# ultrasonic_sensor.net
KiCad netlist of a schematic drawn in Altium Designer
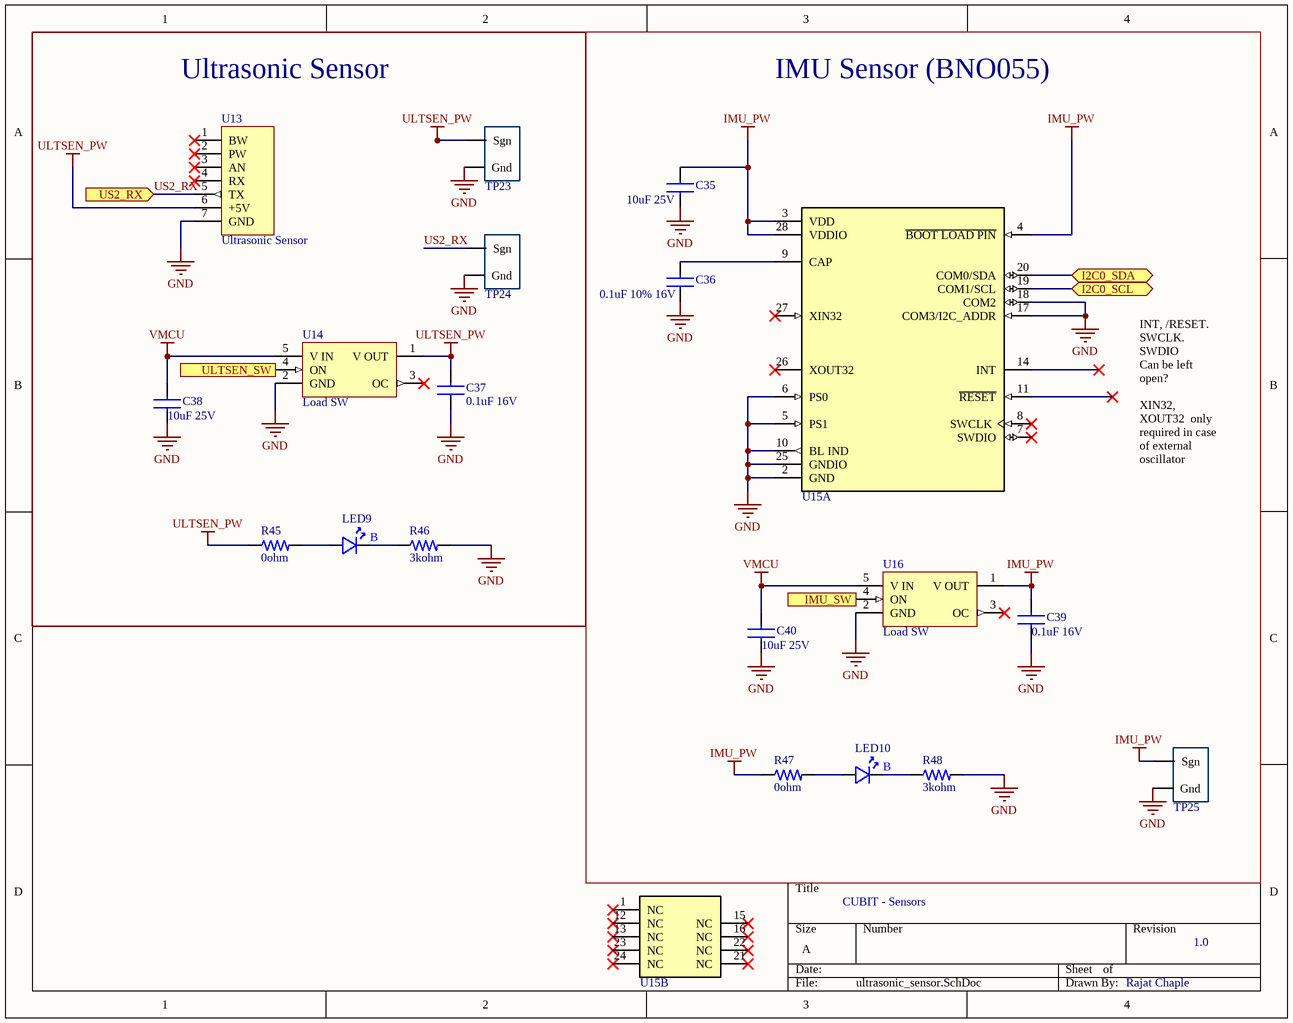
[diagram p0: ultrasonic_sensor.SchDoc]

(export (version "E")
  (design (tool "Eeschema 10.0.6"))
  (components
    (comp (ref "C35")
      (value "10uF 25V")
      (footprint "CAP_0805_02X125")
      (description "Cap 0805 25 V 10 uF ±20% Tolerance X5R Monolithic Ceramic Chip Capacitor")
      (fields
        (field (name "MANUFACTURER") "Murata")
        (field (name "MANUFACTURER PART NUMBER") "GRM21BR61E106KA73K")
      )
      (libsource (lib "LPEDT_proj_lib") (part "GRM21BR61E106KA73K"))
    )
    (comp (ref "C36")
      (value "0.1uF 10% 16V")
      (footprint "CAP_0805_02X125")
      (description "Cap Ceramic 0.1uF 16V X7R 10% SMD 0805 125°C Paper T/R")
      (fields
        (field (name "MANUFACTURER") "KEMET")
        (field (name "MANUFACTURER PART NUMBER") "C0805C104K4RACAUTO")
      )
      (libsource (lib "LPEDT_proj_lib") (part "C0805C104K4RACAUTO"))
    )
    (comp (ref "C37")
      (value "0.1uF 16V")
      (footprint "CAP_0805_02X125")
      (description "Cap Ceramic 0.1uF 16V X7R 10% SMD 0805 125°C Paper T/R")
      (fields
        (field (name "MANUFACTURER") "KEMET")
        (field (name "MANUFACTURER PART NUMBER") "C0805C104K4RACAUTO")
      )
      (libsource (lib "LPEDT_proj_lib") (part "C0805C104K4RACAUTO"))
    )
    (comp (ref "C38")
      (value "10uF 25V")
      (footprint "CAP_0805_02X125")
      (description "Cap 0805 25 V 10 uF ±20% Tolerance X5R Monolithic Ceramic Chip Capacitor")
      (fields
        (field (name "MANUFACTURER") "Murata")
        (field (name "MANUFACTURER PART NUMBER") "GRM21BR61E106KA73K")
      )
      (libsource (lib "LPEDT_proj_lib") (part "GRM21BR61E106KA73K"))
    )
    (comp (ref "C39")
      (value "0.1uF 16V")
      (footprint "CAP_0805_02X125")
      (description "Cap Ceramic 0.1uF 16V X7R 10% SMD 0805 125°C Paper T/R")
      (fields
        (field (name "MANUFACTURER") "KEMET")
        (field (name "MANUFACTURER PART NUMBER") "C0805C104K4RACAUTO")
      )
      (libsource (lib "LPEDT_proj_lib") (part "C0805C104K4RACAUTO"))
    )
    (comp (ref "C40")
      (value "10uF 25V")
      (footprint "CAP_0805_02X125")
      (description "Cap 0805 25 V 10 uF ±20% Tolerance X5R Monolithic Ceramic Chip Capacitor")
      (fields
        (field (name "MANUFACTURER") "Murata")
        (field (name "MANUFACTURER PART NUMBER") "GRM21BR61E106KA73K")
      )
      (libsource (lib "LPEDT_proj_lib") (part "GRM21BR61E106KA73K"))
    )
    (comp (ref "LED9")
      (value "150060BS75000")
      (footprint "LED_0603_RED_WL-SMCW")
      (description "Led, Blue, 470 Nm, 3.2 V, 30 Ma, 145 Mcd Rohs Compliant: Yes")
      (fields (field (name "MANUFACTURER") "Wurth Electronics"))
      (libsource (lib "LPEDT_proj_lib") (part "150060BS75000"))
    )
    (comp (ref "LED10")
      (value "150060BS75000")
      (footprint "LED_0603_RED_WL-SMCW")
      (description "Led, Blue, 470 Nm, 3.2 V, 30 Ma, 145 Mcd Rohs Compliant: Yes")
      (fields (field (name "MANUFACTURER") "Wurth Electronics"))
      (libsource (lib "LPEDT_proj_lib") (part "150060BS75000"))
    )
    (comp (ref "R45")
      (value "0ohm")
      (footprint "CAP_0402_1mm")
      (description "Res 0 Ohms ±5% 0.063 W 0402 Thick Film Surface Mount Chip Resistor")
      (fields
        (field (name "MANUFACTURER") "Samsung")
        (field (name "MANUFACTURER PART NUMBER") "RC1005J000CS")
      )
      (libsource (lib "LPEDT_proj_lib") (part "RC1005J000CS"))
    )
    (comp (ref "R46")
      (value "3kohm")
      (footprint "CAP_0603_1MM")
      (description "Res 3000Ω ± 1.00% 0.1W ± 100ppm/℃ 0603")
      (fields
        (field (name "MANUFACTURER") "Yageo")
        (field (name "MANUFACTURER PART NUMBER") "RC0603FR-073KL")
      )
      (libsource (lib "LPEDT_proj_lib") (part "RC0603FR-073KL"))
    )
    (comp (ref "R47")
      (value "0ohm")
      (footprint "CAP_0402_1mm")
      (description "Res 0 Ohms ±5% 0.063 W 0402 Thick Film Surface Mount Chip Resistor")
      (fields
        (field (name "MANUFACTURER") "Samsung")
        (field (name "MANUFACTURER PART NUMBER") "RC1005J000CS")
      )
      (libsource (lib "LPEDT_proj_lib") (part "RC1005J000CS"))
    )
    (comp (ref "R48")
      (value "3kohm")
      (footprint "CAP_0603_1MM")
      (description "Res 3000Ω ± 1.00% 0.1W ± 100ppm/℃ 0603")
      (fields
        (field (name "MANUFACTURER") "Yageo")
        (field (name "MANUFACTURER PART NUMBER") "RC0603FR-073KL")
      )
      (libsource (lib "LPEDT_proj_lib") (part "RC0603FR-073KL"))
    )
    (comp (ref "TP23")
      (value "10x Probe TP")
      (footprint "TP10x_Probe")
      (description "Test Point 300 mil centers")
      (libsource (lib "LPEDT_proj_lib") (part "TP_10x_Probe"))
    )
    (comp (ref "TP24")
      (value "10x Probe TP")
      (footprint "TP10x_Probe")
      (description "Test Point 300 mil centers")
      (libsource (lib "LPEDT_proj_lib") (part "TP_10x_Probe"))
    )
    (comp (ref "TP25")
      (value "10x Probe TP")
      (footprint "TP10x_Probe")
      (description "Test Point 300 mil centers")
      (libsource (lib "LPEDT_proj_lib") (part "TP_10x_Probe"))
    )
    (comp (ref "U13")
      (value "Ultrasonic Sensor")
      (footprint "7_PIN_100MIL")
      (libsource (lib "LPEDT_proj_lib") (part "Ultrasonic Sensor"))
    )
    (comp (ref "U14")
      (value "Load SW")
      (footprint "SOT65P210X110-5N")
      (description "5.5-V, 0.1-A, 500-mΩ, load switch with current limit and active low enable 5-SC70 -40 to 85")
      (fields
        (field (name "MANUFACTURER") "Texas Instruments")
        (field (name "MANUFACTURER PART NUMBER") "TPS22942DCKR")
      )
      (libsource (lib "LPEDT_proj_lib") (part "TPS22942DCKR"))
    )
    (comp (ref "U15")
      (value "BNO005")
      (footprint "LGA28R50P4X10_380X520X100")
      (libsource (lib "LPEDT_proj_lib") (part "BNO055"))
    )
    (comp (ref "U16")
      (value "Load SW")
      (footprint "SOT65P210X110-5N")
      (description "5.5-V, 0.1-A, 500-mΩ, load switch with current limit and active low enable 5-SC70 -40 to 85")
      (fields
        (field (name "MANUFACTURER") "Texas Instruments")
        (field (name "MANUFACTURER PART NUMBER") "TPS22942DCKR")
      )
      (libsource (lib "LPEDT_proj_lib") (part "TPS22942DCKR"))
    )
  )
  (nets
    (net (code "1") (name "/I2C0_SCL") (class "Default")
      (node (ref "U15") (pin "19") (pinfunction "COM1/SCL_19") (pintype "bidirectional"))
    )
    (net (code "2") (name "/I2C0_SDA") (class "Default")
      (node (ref "U15") (pin "20") (pinfunction "COM0/SDA_20") (pintype "bidirectional"))
    )
    (net (code "3") (name "/IMU_SW") (class "Default")
      (node (ref "U16") (pin "4") (pinfunction "ON_4") (pintype "input"))
    )
    (net (code "4") (name "/ULTSEN_SW") (class "Default")
      (node (ref "U14") (pin "4") (pinfunction "ON_4") (pintype "input"))
    )
    (net (code "5") (name "/US2_RX") (class "Default")
      (node (ref "TP24") (pin "1") (pinfunction "Sgn_1") (pintype "passive"))
      (node (ref "U13") (pin "5") (pinfunction "TX_5") (pintype "output"))
    )
    (net (code "6") (name "GND") (class "Default")
      (node (ref "C35") (pin "2") (pinfunction "2_2") (pintype "passive"))
      (node (ref "C36") (pin "2") (pinfunction "2_2") (pintype "passive"))
      (node (ref "C37") (pin "2") (pinfunction "2_2") (pintype "passive"))
      (node (ref "C38") (pin "2") (pinfunction "2_2") (pintype "passive"))
      (node (ref "C39") (pin "2") (pinfunction "2_2") (pintype "passive"))
      (node (ref "C40") (pin "2") (pinfunction "2_2") (pintype "passive"))
      (node (ref "R46") (pin "2") (pinfunction "2_2") (pintype "passive"))
      (node (ref "R48") (pin "2") (pinfunction "2_2") (pintype "passive"))
      (node (ref "TP23") (pin "2") (pinfunction "Gnd_2") (pintype "passive"))
      (node (ref "TP24") (pin "2") (pinfunction "Gnd_2") (pintype "passive"))
      (node (ref "TP25") (pin "2") (pinfunction "Gnd_2") (pintype "passive"))
      (node (ref "U13") (pin "7") (pinfunction "GND_7") (pintype "power_in"))
      (node (ref "U14") (pin "2") (pinfunction "GND_2") (pintype "power_in"))
      (node (ref "U15") (pin "10") (pinfunction "BL_IND_10") (pintype "output"))
      (node (ref "U15") (pin "17") (pinfunction "COM3/I2C_ADDR_17") (pintype "input"))
      (node (ref "U15") (pin "18") (pinfunction "COM2_18") (pintype "bidirectional"))
      (node (ref "U15") (pin "2") (pinfunction "GND_2") (pintype "power_in"))
      (node (ref "U15") (pin "25") (pinfunction "GNDIO_25") (pintype "power_in"))
      (node (ref "U15") (pin "5") (pinfunction "PS1_5") (pintype "input"))
      (node (ref "U15") (pin "6") (pinfunction "PS0_6") (pintype "input"))
      (node (ref "U16") (pin "2") (pinfunction "GND_2") (pintype "power_in"))
    )
    (net (code "7") (name "IMU_PW") (class "Default")
      (node (ref "C35") (pin "1") (pinfunction "1_1") (pintype "passive"))
      (node (ref "C39") (pin "1") (pinfunction "1_1") (pintype "passive"))
      (node (ref "R47") (pin "1") (pinfunction "1_1") (pintype "passive"))
      (node (ref "TP25") (pin "1") (pinfunction "Sgn_1") (pintype "passive"))
      (node (ref "U15") (pin "28") (pinfunction "VDDIO_28") (pintype "power_in"))
      (node (ref "U15") (pin "3") (pinfunction "VDD_3") (pintype "power_in"))
      (node (ref "U15") (pin "4") (pinfunction "~{BOOT_LOAD_PIN}_4") (pintype "input"))
      (node (ref "U16") (pin "1") (pinfunction "V_OUT_1") (pintype "power_in"))
    )
    (net (code "8") (name "Net-(LED9-PadA)") (class "Default")
      (node (ref "LED9") (pin "A") (pinfunction "A_A") (pintype "passive"))
      (node (ref "R45") (pin "2") (pinfunction "2_2") (pintype "passive"))
    )
    (net (code "9") (name "Net-(LED9-PadC)") (class "Default")
      (node (ref "LED9") (pin "C") (pinfunction "C_C") (pintype "passive"))
      (node (ref "R46") (pin "1") (pinfunction "1_1") (pintype "passive"))
    )
    (net (code "10") (name "Net-(LED10-PadA)") (class "Default")
      (node (ref "LED10") (pin "A") (pinfunction "A_A") (pintype "passive"))
      (node (ref "R47") (pin "2") (pinfunction "2_2") (pintype "passive"))
    )
    (net (code "11") (name "Net-(LED10-PadC)") (class "Default")
      (node (ref "LED10") (pin "C") (pinfunction "C_C") (pintype "passive"))
      (node (ref "R48") (pin "1") (pinfunction "1_1") (pintype "passive"))
    )
    (net (code "12") (name "Net-(U15A-CAP)") (class "Default")
      (node (ref "C36") (pin "1") (pinfunction "1_1") (pintype "passive"))
      (node (ref "U15") (pin "9") (pinfunction "CAP_9") (pintype "passive"))
    )
    (net (code "13") (name "ULTSEN_PW") (class "Default")
      (node (ref "C37") (pin "1") (pinfunction "1_1") (pintype "passive"))
      (node (ref "R45") (pin "1") (pinfunction "1_1") (pintype "passive"))
      (node (ref "TP23") (pin "1") (pinfunction "Sgn_1") (pintype "passive"))
      (node (ref "U13") (pin "6") (pinfunction "+5V_6") (pintype "power_in"))
      (node (ref "U14") (pin "1") (pinfunction "V_OUT_1") (pintype "power_in"))
    )
    (net (code "14") (name "VMCU") (class "Default")
      (node (ref "C38") (pin "1") (pinfunction "1_1") (pintype "passive"))
      (node (ref "C40") (pin "1") (pinfunction "1_1") (pintype "passive"))
      (node (ref "U14") (pin "5") (pinfunction "V_IN_5") (pintype "power_in"))
      (node (ref "U16") (pin "5") (pinfunction "V_IN_5") (pintype "power_in"))
    )
    (net (code "15") (name "unconnected-(U13-AN-Pad3)") (class "Default")
      (node (ref "U13") (pin "3") (pinfunction "AN_3") (pintype "passive+no_connect"))
    )
    (net (code "16") (name "unconnected-(U13-BW-Pad1)") (class "Default")
      (node (ref "U13") (pin "1") (pinfunction "BW_1") (pintype "passive+no_connect"))
    )
    (net (code "17") (name "unconnected-(U13-PW-Pad2)") (class "Default")
      (node (ref "U13") (pin "2") (pinfunction "PW_2") (pintype "passive+no_connect"))
    )
    (net (code "18") (name "unconnected-(U13-RX-Pad4)") (class "Default")
      (node (ref "U13") (pin "4") (pinfunction "RX_4") (pintype "passive+no_connect"))
    )
    (net (code "19") (name "unconnected-(U14-OC-Pad3)") (class "Default")
      (node (ref "U14") (pin "3") (pinfunction "OC_3") (pintype "output+no_connect"))
    )
    (net (code "20") (name "unconnected-(U15A-INT-Pad14)") (class "Default")
      (node (ref "U15") (pin "14") (pinfunction "INT_14") (pintype "passive+no_connect"))
    )
    (net (code "21") (name "unconnected-(U15A-SWCLK-Pad8)") (class "Default")
      (node (ref "U15") (pin "8") (pinfunction "SWCLK_8") (pintype "input+no_connect"))
    )
    (net (code "22") (name "unconnected-(U15A-SWDIO-Pad7)") (class "Default")
      (node (ref "U15") (pin "7") (pinfunction "SWDIO_7") (pintype "bidirectional+no_connect"))
    )
    (net (code "23") (name "unconnected-(U15A-XIN32-Pad27)") (class "Default")
      (node (ref "U15") (pin "27") (pinfunction "XIN32_27") (pintype "input+no_connect"))
    )
    (net (code "24") (name "unconnected-(U15A-XOUT32-Pad26)") (class "Default")
      (node (ref "U15") (pin "26") (pinfunction "XOUT32_26") (pintype "passive+no_connect"))
    )
    (net (code "25") (name "unconnected-(U15A-~{RESET}-Pad11)") (class "Default")
      (node (ref "U15") (pin "11") (pinfunction "~{RESET}_11") (pintype "input+no_connect"))
    )
    (net (code "26") (name "unconnected-(U15B-NC-Pad1)") (class "Default")
      (node (ref "U15") (pin "1") (pinfunction "NC_1") (pintype "passive+no_connect"))
    )
    (net (code "27") (name "unconnected-(U15B-NC-Pad12)") (class "Default")
      (node (ref "U15") (pin "12") (pinfunction "NC_12") (pintype "passive+no_connect"))
    )
    (net (code "28") (name "unconnected-(U15B-NC-Pad13)") (class "Default")
      (node (ref "U15") (pin "13") (pinfunction "NC_13") (pintype "passive+no_connect"))
    )
    (net (code "29") (name "unconnected-(U15B-NC-Pad15)") (class "Default")
      (node (ref "U15") (pin "15") (pinfunction "NC_15") (pintype "passive+no_connect"))
    )
    (net (code "30") (name "unconnected-(U15B-NC-Pad16)") (class "Default")
      (node (ref "U15") (pin "16") (pinfunction "NC_16") (pintype "passive+no_connect"))
    )
    (net (code "31") (name "unconnected-(U15B-NC-Pad21)") (class "Default")
      (node (ref "U15") (pin "21") (pinfunction "NC_21") (pintype "passive+no_connect"))
    )
    (net (code "32") (name "unconnected-(U15B-NC-Pad22)") (class "Default")
      (node (ref "U15") (pin "22") (pinfunction "NC_22") (pintype "passive+no_connect"))
    )
    (net (code "33") (name "unconnected-(U15B-NC-Pad23)") (class "Default")
      (node (ref "U15") (pin "23") (pinfunction "NC_23") (pintype "passive+no_connect"))
    )
    (net (code "34") (name "unconnected-(U15B-NC-Pad24)") (class "Default")
      (node (ref "U15") (pin "24") (pinfunction "NC_24") (pintype "passive+no_connect"))
    )
    (net (code "35") (name "unconnected-(U16-OC-Pad3)") (class "Default")
      (node (ref "U16") (pin "3") (pinfunction "OC_3") (pintype "output+no_connect"))
    )
  )
)
